# 04_-_Keyboard_Matrix_2.net
KiCad netlist of a schematic drawn in Altium Designer
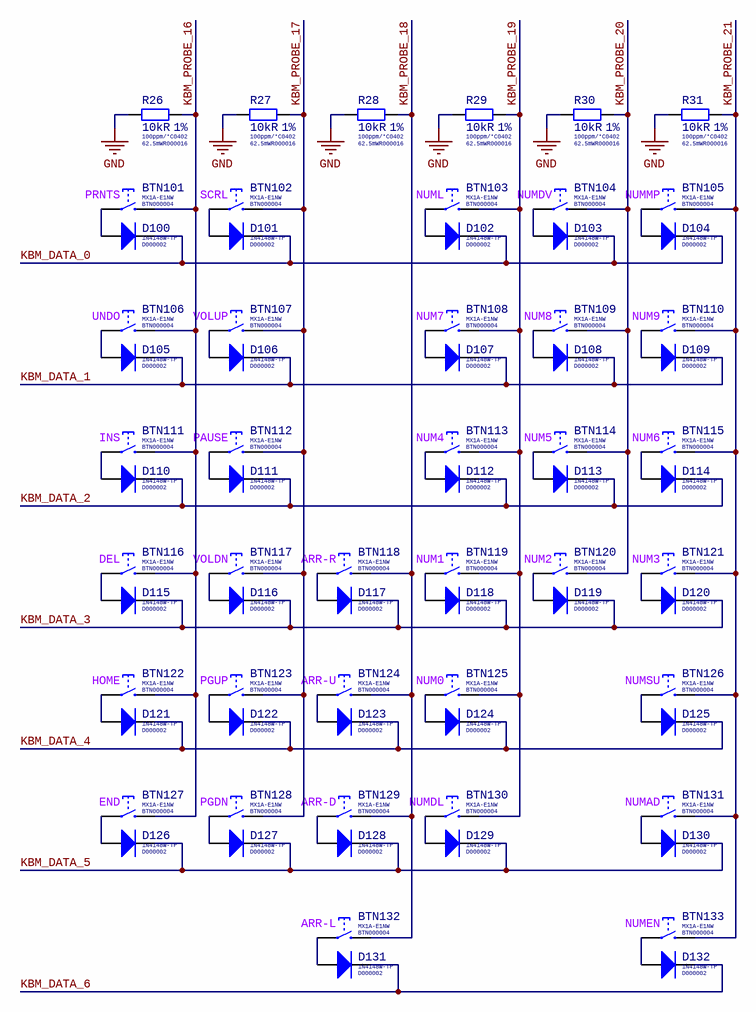
[diagram p0: [04] - Keyboard Matrix 2.SchDoc]

(export (version "E")
  (design (tool "Eeschema 10.0.6"))
  (components
    (comp (ref "BTN101")
      (value "MX1A-E1NW")
      (footprint "BTN-THT-MX-CHERRY")
      (description "BTN CHERRY MX BLUE SPST-NO 12V 10mA")
      (fields
        (field (name "MANUFACTURER") "Cherry")
        (field (name "INTERNAL PART NUMBER") "BTN000004")
        (field (name "KEY FUNCTION") "PRNTS")
      )
      (libsource (lib "Altium_Lib_Standard") (part "MX1A-E1NW"))
    )
    (comp (ref "BTN102")
      (value "MX1A-E1NW")
      (footprint "BTN-THT-MX-CHERRY")
      (description "BTN CHERRY MX BLUE SPST-NO 12V 10mA")
      (fields
        (field (name "MANUFACTURER") "Cherry")
        (field (name "INTERNAL PART NUMBER") "BTN000004")
        (field (name "KEY FUNCTION") "SCRL")
      )
      (libsource (lib "Altium_Lib_Standard") (part "MX1A-E1NW"))
    )
    (comp (ref "BTN103")
      (value "MX1A-E1NW")
      (footprint "BTN-THT-MX-CHERRY")
      (description "BTN CHERRY MX BLUE SPST-NO 12V 10mA")
      (fields
        (field (name "MANUFACTURER") "Cherry")
        (field (name "INTERNAL PART NUMBER") "BTN000004")
        (field (name "KEY FUNCTION") "NUML")
      )
      (libsource (lib "Altium_Lib_Standard") (part "MX1A-E1NW"))
    )
    (comp (ref "BTN104")
      (value "MX1A-E1NW")
      (footprint "BTN-THT-MX-CHERRY")
      (description "BTN CHERRY MX BLUE SPST-NO 12V 10mA")
      (fields
        (field (name "MANUFACTURER") "Cherry")
        (field (name "INTERNAL PART NUMBER") "BTN000004")
        (field (name "KEY FUNCTION") "NUMDV")
      )
      (libsource (lib "Altium_Lib_Standard") (part "MX1A-E1NW"))
    )
    (comp (ref "BTN105")
      (value "MX1A-E1NW")
      (footprint "BTN-THT-MX-CHERRY")
      (description "BTN CHERRY MX BLUE SPST-NO 12V 10mA")
      (fields
        (field (name "MANUFACTURER") "Cherry")
        (field (name "INTERNAL PART NUMBER") "BTN000004")
        (field (name "KEY FUNCTION") "NUMMP")
      )
      (libsource (lib "Altium_Lib_Standard") (part "MX1A-E1NW"))
    )
    (comp (ref "BTN106")
      (value "MX1A-E1NW")
      (footprint "BTN-THT-MX-CHERRY")
      (description "BTN CHERRY MX BLUE SPST-NO 12V 10mA")
      (fields
        (field (name "MANUFACTURER") "Cherry")
        (field (name "INTERNAL PART NUMBER") "BTN000004")
        (field (name "KEY FUNCTION") "UNDO")
      )
      (libsource (lib "Altium_Lib_Standard") (part "MX1A-E1NW"))
    )
    (comp (ref "BTN107")
      (value "MX1A-E1NW")
      (footprint "BTN-THT-MX-CHERRY")
      (description "BTN CHERRY MX BLUE SPST-NO 12V 10mA")
      (fields
        (field (name "MANUFACTURER") "Cherry")
        (field (name "INTERNAL PART NUMBER") "BTN000004")
        (field (name "KEY FUNCTION") "VOLUP")
      )
      (libsource (lib "Altium_Lib_Standard") (part "MX1A-E1NW"))
    )
    (comp (ref "BTN108")
      (value "MX1A-E1NW")
      (footprint "BTN-THT-MX-CHERRY")
      (description "BTN CHERRY MX BLUE SPST-NO 12V 10mA")
      (fields
        (field (name "MANUFACTURER") "Cherry")
        (field (name "INTERNAL PART NUMBER") "BTN000004")
        (field (name "KEY FUNCTION") "NUM7")
      )
      (libsource (lib "Altium_Lib_Standard") (part "MX1A-E1NW"))
    )
    (comp (ref "BTN109")
      (value "MX1A-E1NW")
      (footprint "BTN-THT-MX-CHERRY")
      (description "BTN CHERRY MX BLUE SPST-NO 12V 10mA")
      (fields
        (field (name "MANUFACTURER") "Cherry")
        (field (name "INTERNAL PART NUMBER") "BTN000004")
        (field (name "KEY FUNCTION") "NUM8")
      )
      (libsource (lib "Altium_Lib_Standard") (part "MX1A-E1NW"))
    )
    (comp (ref "BTN110")
      (value "MX1A-E1NW")
      (footprint "BTN-THT-MX-CHERRY")
      (description "BTN CHERRY MX BLUE SPST-NO 12V 10mA")
      (fields
        (field (name "MANUFACTURER") "Cherry")
        (field (name "INTERNAL PART NUMBER") "BTN000004")
        (field (name "KEY FUNCTION") "NUM9")
      )
      (libsource (lib "Altium_Lib_Standard") (part "MX1A-E1NW"))
    )
    (comp (ref "BTN111")
      (value "MX1A-E1NW")
      (footprint "BTN-THT-MX-CHERRY")
      (description "BTN CHERRY MX BLUE SPST-NO 12V 10mA")
      (fields
        (field (name "MANUFACTURER") "Cherry")
        (field (name "INTERNAL PART NUMBER") "BTN000004")
        (field (name "KEY FUNCTION") "INS")
      )
      (libsource (lib "Altium_Lib_Standard") (part "MX1A-E1NW"))
    )
    (comp (ref "BTN112")
      (value "MX1A-E1NW")
      (footprint "BTN-THT-MX-CHERRY")
      (description "BTN CHERRY MX BLUE SPST-NO 12V 10mA")
      (fields
        (field (name "MANUFACTURER") "Cherry")
        (field (name "INTERNAL PART NUMBER") "BTN000004")
        (field (name "KEY FUNCTION") "PAUSE")
      )
      (libsource (lib "Altium_Lib_Standard") (part "MX1A-E1NW"))
    )
    (comp (ref "BTN113")
      (value "MX1A-E1NW")
      (footprint "BTN-THT-MX-CHERRY")
      (description "BTN CHERRY MX BLUE SPST-NO 12V 10mA")
      (fields
        (field (name "MANUFACTURER") "Cherry")
        (field (name "INTERNAL PART NUMBER") "BTN000004")
        (field (name "KEY FUNCTION") "NUM4")
      )
      (libsource (lib "Altium_Lib_Standard") (part "MX1A-E1NW"))
    )
    (comp (ref "BTN114")
      (value "MX1A-E1NW")
      (footprint "BTN-THT-MX-CHERRY")
      (description "BTN CHERRY MX BLUE SPST-NO 12V 10mA")
      (fields
        (field (name "MANUFACTURER") "Cherry")
        (field (name "INTERNAL PART NUMBER") "BTN000004")
        (field (name "KEY FUNCTION") "NUM5")
      )
      (libsource (lib "Altium_Lib_Standard") (part "MX1A-E1NW"))
    )
    (comp (ref "BTN115")
      (value "MX1A-E1NW")
      (footprint "BTN-THT-MX-CHERRY")
      (description "BTN CHERRY MX BLUE SPST-NO 12V 10mA")
      (fields
        (field (name "MANUFACTURER") "Cherry")
        (field (name "INTERNAL PART NUMBER") "BTN000004")
        (field (name "KEY FUNCTION") "NUM6")
      )
      (libsource (lib "Altium_Lib_Standard") (part "MX1A-E1NW"))
    )
    (comp (ref "BTN116")
      (value "MX1A-E1NW")
      (footprint "BTN-THT-MX-CHERRY")
      (description "BTN CHERRY MX BLUE SPST-NO 12V 10mA")
      (fields
        (field (name "MANUFACTURER") "Cherry")
        (field (name "INTERNAL PART NUMBER") "BTN000004")
        (field (name "KEY FUNCTION") "DEL")
      )
      (libsource (lib "Altium_Lib_Standard") (part "MX1A-E1NW"))
    )
    (comp (ref "BTN117")
      (value "MX1A-E1NW")
      (footprint "BTN-THT-MX-CHERRY")
      (description "BTN CHERRY MX BLUE SPST-NO 12V 10mA")
      (fields
        (field (name "MANUFACTURER") "Cherry")
        (field (name "INTERNAL PART NUMBER") "BTN000004")
        (field (name "KEY FUNCTION") "VOLDN")
      )
      (libsource (lib "Altium_Lib_Standard") (part "MX1A-E1NW"))
    )
    (comp (ref "BTN118")
      (value "MX1A-E1NW")
      (footprint "BTN-THT-MX-CHERRY")
      (description "BTN CHERRY MX BLUE SPST-NO 12V 10mA")
      (fields
        (field (name "MANUFACTURER") "Cherry")
        (field (name "INTERNAL PART NUMBER") "BTN000004")
        (field (name "KEY FUNCTION") "ARR-R")
      )
      (libsource (lib "Altium_Lib_Standard") (part "MX1A-E1NW"))
    )
    (comp (ref "BTN119")
      (value "MX1A-E1NW")
      (footprint "BTN-THT-MX-CHERRY")
      (description "BTN CHERRY MX BLUE SPST-NO 12V 10mA")
      (fields
        (field (name "MANUFACTURER") "Cherry")
        (field (name "INTERNAL PART NUMBER") "BTN000004")
        (field (name "KEY FUNCTION") "NUM1")
      )
      (libsource (lib "Altium_Lib_Standard") (part "MX1A-E1NW"))
    )
    (comp (ref "BTN120")
      (value "MX1A-E1NW")
      (footprint "BTN-THT-MX-CHERRY")
      (description "BTN CHERRY MX BLUE SPST-NO 12V 10mA")
      (fields
        (field (name "MANUFACTURER") "Cherry")
        (field (name "INTERNAL PART NUMBER") "BTN000004")
        (field (name "KEY FUNCTION") "NUM2")
      )
      (libsource (lib "Altium_Lib_Standard") (part "MX1A-E1NW"))
    )
    (comp (ref "BTN121")
      (value "MX1A-E1NW")
      (footprint "BTN-THT-MX-CHERRY")
      (description "BTN CHERRY MX BLUE SPST-NO 12V 10mA")
      (fields
        (field (name "MANUFACTURER") "Cherry")
        (field (name "INTERNAL PART NUMBER") "BTN000004")
        (field (name "KEY FUNCTION") "NUM3")
      )
      (libsource (lib "Altium_Lib_Standard") (part "MX1A-E1NW"))
    )
    (comp (ref "BTN122")
      (value "MX1A-E1NW")
      (footprint "BTN-THT-MX-CHERRY")
      (description "BTN CHERRY MX BLUE SPST-NO 12V 10mA")
      (fields
        (field (name "MANUFACTURER") "Cherry")
        (field (name "INTERNAL PART NUMBER") "BTN000004")
        (field (name "KEY FUNCTION") "HOME")
      )
      (libsource (lib "Altium_Lib_Standard") (part "MX1A-E1NW"))
    )
    (comp (ref "BTN123")
      (value "MX1A-E1NW")
      (footprint "BTN-THT-MX-CHERRY")
      (description "BTN CHERRY MX BLUE SPST-NO 12V 10mA")
      (fields
        (field (name "MANUFACTURER") "Cherry")
        (field (name "INTERNAL PART NUMBER") "BTN000004")
        (field (name "KEY FUNCTION") "PGUP")
      )
      (libsource (lib "Altium_Lib_Standard") (part "MX1A-E1NW"))
    )
    (comp (ref "BTN124")
      (value "MX1A-E1NW")
      (footprint "BTN-THT-MX-CHERRY")
      (description "BTN CHERRY MX BLUE SPST-NO 12V 10mA")
      (fields
        (field (name "MANUFACTURER") "Cherry")
        (field (name "INTERNAL PART NUMBER") "BTN000004")
        (field (name "KEY FUNCTION") "ARR-U")
      )
      (libsource (lib "Altium_Lib_Standard") (part "MX1A-E1NW"))
    )
    (comp (ref "BTN125")
      (value "MX1A-E1NW")
      (footprint "BTN-THT-MX-CHERRY")
      (description "BTN CHERRY MX BLUE SPST-NO 12V 10mA")
      (fields
        (field (name "MANUFACTURER") "Cherry")
        (field (name "INTERNAL PART NUMBER") "BTN000004")
        (field (name "KEY FUNCTION") "NUM0")
      )
      (libsource (lib "Altium_Lib_Standard") (part "MX1A-E1NW"))
    )
    (comp (ref "BTN126")
      (value "MX1A-E1NW")
      (footprint "BTN-THT-MX-CHERRY")
      (description "BTN CHERRY MX BLUE SPST-NO 12V 10mA")
      (fields
        (field (name "MANUFACTURER") "Cherry")
        (field (name "INTERNAL PART NUMBER") "BTN000004")
        (field (name "KEY FUNCTION") "NUMSU")
      )
      (libsource (lib "Altium_Lib_Standard") (part "MX1A-E1NW"))
    )
    (comp (ref "BTN127")
      (value "MX1A-E1NW")
      (footprint "BTN-THT-MX-CHERRY")
      (description "BTN CHERRY MX BLUE SPST-NO 12V 10mA")
      (fields
        (field (name "MANUFACTURER") "Cherry")
        (field (name "INTERNAL PART NUMBER") "BTN000004")
        (field (name "KEY FUNCTION") "END")
      )
      (libsource (lib "Altium_Lib_Standard") (part "MX1A-E1NW"))
    )
    (comp (ref "BTN128")
      (value "MX1A-E1NW")
      (footprint "BTN-THT-MX-CHERRY")
      (description "BTN CHERRY MX BLUE SPST-NO 12V 10mA")
      (fields
        (field (name "MANUFACTURER") "Cherry")
        (field (name "INTERNAL PART NUMBER") "BTN000004")
        (field (name "KEY FUNCTION") "PGDN")
      )
      (libsource (lib "Altium_Lib_Standard") (part "MX1A-E1NW"))
    )
    (comp (ref "BTN129")
      (value "MX1A-E1NW")
      (footprint "BTN-THT-MX-CHERRY")
      (description "BTN CHERRY MX BLUE SPST-NO 12V 10mA")
      (fields
        (field (name "MANUFACTURER") "Cherry")
        (field (name "INTERNAL PART NUMBER") "BTN000004")
        (field (name "KEY FUNCTION") "ARR-D")
      )
      (libsource (lib "Altium_Lib_Standard") (part "MX1A-E1NW"))
    )
    (comp (ref "BTN130")
      (value "MX1A-E1NW")
      (footprint "BTN-THT-MX-CHERRY")
      (description "BTN CHERRY MX BLUE SPST-NO 12V 10mA")
      (fields
        (field (name "MANUFACTURER") "Cherry")
        (field (name "INTERNAL PART NUMBER") "BTN000004")
        (field (name "KEY FUNCTION") "NUMDL")
      )
      (libsource (lib "Altium_Lib_Standard") (part "MX1A-E1NW"))
    )
    (comp (ref "BTN131")
      (value "MX1A-E1NW")
      (footprint "BTN-THT-MX-CHERRY")
      (description "BTN CHERRY MX BLUE SPST-NO 12V 10mA")
      (fields
        (field (name "MANUFACTURER") "Cherry")
        (field (name "INTERNAL PART NUMBER") "BTN000004")
        (field (name "KEY FUNCTION") "NUMAD")
      )
      (libsource (lib "Altium_Lib_Standard") (part "MX1A-E1NW"))
    )
    (comp (ref "BTN132")
      (value "MX1A-E1NW")
      (footprint "BTN-THT-MX-CHERRY")
      (description "BTN CHERRY MX BLUE SPST-NO 12V 10mA")
      (fields
        (field (name "MANUFACTURER") "Cherry")
        (field (name "INTERNAL PART NUMBER") "BTN000004")
        (field (name "KEY FUNCTION") "ARR-L")
      )
      (libsource (lib "Altium_Lib_Standard") (part "MX1A-E1NW"))
    )
    (comp (ref "BTN133")
      (value "MX1A-E1NW")
      (footprint "BTN-THT-MX-CHERRY")
      (description "BTN CHERRY MX BLUE SPST-NO 12V 10mA")
      (fields
        (field (name "MANUFACTURER") "Cherry")
        (field (name "INTERNAL PART NUMBER") "BTN000004")
        (field (name "KEY FUNCTION") "NUMEN")
      )
      (libsource (lib "Altium_Lib_Standard") (part "MX1A-E1NW"))
    )
    (comp (ref "D100")
      (value "1N4148W-TP")
      (footprint "D-SMD-SOD-123-MICRO-COMMERCIAL-COMPONENTS")
      (description "DIODE GEN-PURP 100V 150mA 1V25@150mA SMD SOD-23")
      (fields (field (name "MANUFACTURER") "MCC") (field (name "INTERNAL PART NUMBER") "D000002"))
      (libsource (lib "Altium_Lib_Standard") (part "1N4148W-TP"))
    )
    (comp (ref "D101")
      (value "1N4148W-TP")
      (footprint "D-SMD-SOD-123-MICRO-COMMERCIAL-COMPONENTS")
      (description "DIODE GEN-PURP 100V 150mA 1V25@150mA SMD SOD-23")
      (fields (field (name "MANUFACTURER") "MCC") (field (name "INTERNAL PART NUMBER") "D000002"))
      (libsource (lib "Altium_Lib_Standard") (part "1N4148W-TP"))
    )
    (comp (ref "D102")
      (value "1N4148W-TP")
      (footprint "D-SMD-SOD-123-MICRO-COMMERCIAL-COMPONENTS")
      (description "DIODE GEN-PURP 100V 150mA 1V25@150mA SMD SOD-23")
      (fields (field (name "MANUFACTURER") "MCC") (field (name "INTERNAL PART NUMBER") "D000002"))
      (libsource (lib "Altium_Lib_Standard") (part "1N4148W-TP"))
    )
    (comp (ref "D103")
      (value "1N4148W-TP")
      (footprint "D-SMD-SOD-123-MICRO-COMMERCIAL-COMPONENTS")
      (description "DIODE GEN-PURP 100V 150mA 1V25@150mA SMD SOD-23")
      (fields (field (name "MANUFACTURER") "MCC") (field (name "INTERNAL PART NUMBER") "D000002"))
      (libsource (lib "Altium_Lib_Standard") (part "1N4148W-TP"))
    )
    (comp (ref "D104")
      (value "1N4148W-TP")
      (footprint "D-SMD-SOD-123-MICRO-COMMERCIAL-COMPONENTS")
      (description "DIODE GEN-PURP 100V 150mA 1V25@150mA SMD SOD-23")
      (fields (field (name "MANUFACTURER") "MCC") (field (name "INTERNAL PART NUMBER") "D000002"))
      (libsource (lib "Altium_Lib_Standard") (part "1N4148W-TP"))
    )
    (comp (ref "D105")
      (value "1N4148W-TP")
      (footprint "D-SMD-SOD-123-MICRO-COMMERCIAL-COMPONENTS")
      (description "DIODE GEN-PURP 100V 150mA 1V25@150mA SMD SOD-23")
      (fields (field (name "MANUFACTURER") "MCC") (field (name "INTERNAL PART NUMBER") "D000002"))
      (libsource (lib "Altium_Lib_Standard") (part "1N4148W-TP"))
    )
    (comp (ref "D106")
      (value "1N4148W-TP")
      (footprint "D-SMD-SOD-123-MICRO-COMMERCIAL-COMPONENTS")
      (description "DIODE GEN-PURP 100V 150mA 1V25@150mA SMD SOD-23")
      (fields (field (name "MANUFACTURER") "MCC") (field (name "INTERNAL PART NUMBER") "D000002"))
      (libsource (lib "Altium_Lib_Standard") (part "1N4148W-TP"))
    )
    (comp (ref "D107")
      (value "1N4148W-TP")
      (footprint "D-SMD-SOD-123-MICRO-COMMERCIAL-COMPONENTS")
      (description "DIODE GEN-PURP 100V 150mA 1V25@150mA SMD SOD-23")
      (fields (field (name "MANUFACTURER") "MCC") (field (name "INTERNAL PART NUMBER") "D000002"))
      (libsource (lib "Altium_Lib_Standard") (part "1N4148W-TP"))
    )
    (comp (ref "D108")
      (value "1N4148W-TP")
      (footprint "D-SMD-SOD-123-MICRO-COMMERCIAL-COMPONENTS")
      (description "DIODE GEN-PURP 100V 150mA 1V25@150mA SMD SOD-23")
      (fields (field (name "MANUFACTURER") "MCC") (field (name "INTERNAL PART NUMBER") "D000002"))
      (libsource (lib "Altium_Lib_Standard") (part "1N4148W-TP"))
    )
    (comp (ref "D109")
      (value "1N4148W-TP")
      (footprint "D-SMD-SOD-123-MICRO-COMMERCIAL-COMPONENTS")
      (description "DIODE GEN-PURP 100V 150mA 1V25@150mA SMD SOD-23")
      (fields (field (name "MANUFACTURER") "MCC") (field (name "INTERNAL PART NUMBER") "D000002"))
      (libsource (lib "Altium_Lib_Standard") (part "1N4148W-TP"))
    )
    (comp (ref "D110")
      (value "1N4148W-TP")
      (footprint "D-SMD-SOD-123-MICRO-COMMERCIAL-COMPONENTS")
      (description "DIODE GEN-PURP 100V 150mA 1V25@150mA SMD SOD-23")
      (fields (field (name "MANUFACTURER") "MCC") (field (name "INTERNAL PART NUMBER") "D000002"))
      (libsource (lib "Altium_Lib_Standard") (part "1N4148W-TP"))
    )
    (comp (ref "D111")
      (value "1N4148W-TP")
      (footprint "D-SMD-SOD-123-MICRO-COMMERCIAL-COMPONENTS")
      (description "DIODE GEN-PURP 100V 150mA 1V25@150mA SMD SOD-23")
      (fields (field (name "MANUFACTURER") "MCC") (field (name "INTERNAL PART NUMBER") "D000002"))
      (libsource (lib "Altium_Lib_Standard") (part "1N4148W-TP"))
    )
    (comp (ref "D112")
      (value "1N4148W-TP")
      (footprint "D-SMD-SOD-123-MICRO-COMMERCIAL-COMPONENTS")
      (description "DIODE GEN-PURP 100V 150mA 1V25@150mA SMD SOD-23")
      (fields (field (name "MANUFACTURER") "MCC") (field (name "INTERNAL PART NUMBER") "D000002"))
      (libsource (lib "Altium_Lib_Standard") (part "1N4148W-TP"))
    )
    (comp (ref "D113")
      (value "1N4148W-TP")
      (footprint "D-SMD-SOD-123-MICRO-COMMERCIAL-COMPONENTS")
      (description "DIODE GEN-PURP 100V 150mA 1V25@150mA SMD SOD-23")
      (fields (field (name "MANUFACTURER") "MCC") (field (name "INTERNAL PART NUMBER") "D000002"))
      (libsource (lib "Altium_Lib_Standard") (part "1N4148W-TP"))
    )
    (comp (ref "D114")
      (value "1N4148W-TP")
      (footprint "D-SMD-SOD-123-MICRO-COMMERCIAL-COMPONENTS")
      (description "DIODE GEN-PURP 100V 150mA 1V25@150mA SMD SOD-23")
      (fields (field (name "MANUFACTURER") "MCC") (field (name "INTERNAL PART NUMBER") "D000002"))
      (libsource (lib "Altium_Lib_Standard") (part "1N4148W-TP"))
    )
    (comp (ref "D115")
      (value "1N4148W-TP")
      (footprint "D-SMD-SOD-123-MICRO-COMMERCIAL-COMPONENTS")
      (description "DIODE GEN-PURP 100V 150mA 1V25@150mA SMD SOD-23")
      (fields (field (name "MANUFACTURER") "MCC") (field (name "INTERNAL PART NUMBER") "D000002"))
      (libsource (lib "Altium_Lib_Standard") (part "1N4148W-TP"))
    )
    (comp (ref "D116")
      (value "1N4148W-TP")
      (footprint "D-SMD-SOD-123-MICRO-COMMERCIAL-COMPONENTS")
      (description "DIODE GEN-PURP 100V 150mA 1V25@150mA SMD SOD-23")
      (fields (field (name "MANUFACTURER") "MCC") (field (name "INTERNAL PART NUMBER") "D000002"))
      (libsource (lib "Altium_Lib_Standard") (part "1N4148W-TP"))
    )
    (comp (ref "D117")
      (value "1N4148W-TP")
      (footprint "D-SMD-SOD-123-MICRO-COMMERCIAL-COMPONENTS")
      (description "DIODE GEN-PURP 100V 150mA 1V25@150mA SMD SOD-23")
      (fields (field (name "MANUFACTURER") "MCC") (field (name "INTERNAL PART NUMBER") "D000002"))
      (libsource (lib "Altium_Lib_Standard") (part "1N4148W-TP"))
    )
    (comp (ref "D118")
      (value "1N4148W-TP")
      (footprint "D-SMD-SOD-123-MICRO-COMMERCIAL-COMPONENTS")
      (description "DIODE GEN-PURP 100V 150mA 1V25@150mA SMD SOD-23")
      (fields (field (name "MANUFACTURER") "MCC") (field (name "INTERNAL PART NUMBER") "D000002"))
      (libsource (lib "Altium_Lib_Standard") (part "1N4148W-TP"))
    )
    (comp (ref "D119")
      (value "1N4148W-TP")
      (footprint "D-SMD-SOD-123-MICRO-COMMERCIAL-COMPONENTS")
      (description "DIODE GEN-PURP 100V 150mA 1V25@150mA SMD SOD-23")
      (fields (field (name "MANUFACTURER") "MCC") (field (name "INTERNAL PART NUMBER") "D000002"))
      (libsource (lib "Altium_Lib_Standard") (part "1N4148W-TP"))
    )
    (comp (ref "D120")
      (value "1N4148W-TP")
      (footprint "D-SMD-SOD-123-MICRO-COMMERCIAL-COMPONENTS")
      (description "DIODE GEN-PURP 100V 150mA 1V25@150mA SMD SOD-23")
      (fields (field (name "MANUFACTURER") "MCC") (field (name "INTERNAL PART NUMBER") "D000002"))
      (libsource (lib "Altium_Lib_Standard") (part "1N4148W-TP"))
    )
    (comp (ref "D121")
      (value "1N4148W-TP")
      (footprint "D-SMD-SOD-123-MICRO-COMMERCIAL-COMPONENTS")
      (description "DIODE GEN-PURP 100V 150mA 1V25@150mA SMD SOD-23")
      (fields (field (name "MANUFACTURER") "MCC") (field (name "INTERNAL PART NUMBER") "D000002"))
      (libsource (lib "Altium_Lib_Standard") (part "1N4148W-TP"))
    )
    (comp (ref "D122")
      (value "1N4148W-TP")
      (footprint "D-SMD-SOD-123-MICRO-COMMERCIAL-COMPONENTS")
      (description "DIODE GEN-PURP 100V 150mA 1V25@150mA SMD SOD-23")
      (fields (field (name "MANUFACTURER") "MCC") (field (name "INTERNAL PART NUMBER") "D000002"))
      (libsource (lib "Altium_Lib_Standard") (part "1N4148W-TP"))
    )
    (comp (ref "D123")
      (value "1N4148W-TP")
      (footprint "D-SMD-SOD-123-MICRO-COMMERCIAL-COMPONENTS")
      (description "DIODE GEN-PURP 100V 150mA 1V25@150mA SMD SOD-23")
      (fields (field (name "MANUFACTURER") "MCC") (field (name "INTERNAL PART NUMBER") "D000002"))
      (libsource (lib "Altium_Lib_Standard") (part "1N4148W-TP"))
    )
    (comp (ref "D124")
      (value "1N4148W-TP")
      (footprint "D-SMD-SOD-123-MICRO-COMMERCIAL-COMPONENTS")
      (description "DIODE GEN-PURP 100V 150mA 1V25@150mA SMD SOD-23")
      (fields (field (name "MANUFACTURER") "MCC") (field (name "INTERNAL PART NUMBER") "D000002"))
      (libsource (lib "Altium_Lib_Standard") (part "1N4148W-TP"))
    )
    (comp (ref "D125")
      (value "1N4148W-TP")
      (footprint "D-SMD-SOD-123-MICRO-COMMERCIAL-COMPONENTS")
      (description "DIODE GEN-PURP 100V 150mA 1V25@150mA SMD SOD-23")
      (fields (field (name "MANUFACTURER") "MCC") (field (name "INTERNAL PART NUMBER") "D000002"))
      (libsource (lib "Altium_Lib_Standard") (part "1N4148W-TP"))
    )
    (comp (ref "D126")
      (value "1N4148W-TP")
      (footprint "D-SMD-SOD-123-MICRO-COMMERCIAL-COMPONENTS")
      (description "DIODE GEN-PURP 100V 150mA 1V25@150mA SMD SOD-23")
      (fields (field (name "MANUFACTURER") "MCC") (field (name "INTERNAL PART NUMBER") "D000002"))
      (libsource (lib "Altium_Lib_Standard") (part "1N4148W-TP"))
    )
    (comp (ref "D127")
      (value "1N4148W-TP")
      (footprint "D-SMD-SOD-123-MICRO-COMMERCIAL-COMPONENTS")
      (description "DIODE GEN-PURP 100V 150mA 1V25@150mA SMD SOD-23")
      (fields (field (name "MANUFACTURER") "MCC") (field (name "INTERNAL PART NUMBER") "D000002"))
      (libsource (lib "Altium_Lib_Standard") (part "1N4148W-TP"))
    )
    (comp (ref "D128")
      (value "1N4148W-TP")
      (footprint "D-SMD-SOD-123-MICRO-COMMERCIAL-COMPONENTS")
      (description "DIODE GEN-PURP 100V 150mA 1V25@150mA SMD SOD-23")
      (fields (field (name "MANUFACTURER") "MCC") (field (name "INTERNAL PART NUMBER") "D000002"))
      (libsource (lib "Altium_Lib_Standard") (part "1N4148W-TP"))
    )
    (comp (ref "D129")
      (value "1N4148W-TP")
      (footprint "D-SMD-SOD-123-MICRO-COMMERCIAL-COMPONENTS")
      (description "DIODE GEN-PURP 100V 150mA 1V25@150mA SMD SOD-23")
      (fields (field (name "MANUFACTURER") "MCC") (field (name "INTERNAL PART NUMBER") "D000002"))
      (libsource (lib "Altium_Lib_Standard") (part "1N4148W-TP"))
    )
    (comp (ref "D130")
      (value "1N4148W-TP")
      (footprint "D-SMD-SOD-123-MICRO-COMMERCIAL-COMPONENTS")
      (description "DIODE GEN-PURP 100V 150mA 1V25@150mA SMD SOD-23")
      (fields (field (name "MANUFACTURER") "MCC") (field (name "INTERNAL PART NUMBER") "D000002"))
      (libsource (lib "Altium_Lib_Standard") (part "1N4148W-TP"))
    )
    (comp (ref "D131")
      (value "1N4148W-TP")
      (footprint "D-SMD-SOD-123-MICRO-COMMERCIAL-COMPONENTS")
      (description "DIODE GEN-PURP 100V 150mA 1V25@150mA SMD SOD-23")
      (fields (field (name "MANUFACTURER") "MCC") (field (name "INTERNAL PART NUMBER") "D000002"))
      (libsource (lib "Altium_Lib_Standard") (part "1N4148W-TP"))
    )
    (comp (ref "D132")
      (value "1N4148W-TP")
      (footprint "D-SMD-SOD-123-MICRO-COMMERCIAL-COMPONENTS")
      (description "DIODE GEN-PURP 100V 150mA 1V25@150mA SMD SOD-23")
      (fields (field (name "MANUFACTURER") "MCC") (field (name "INTERNAL PART NUMBER") "D000002"))
      (libsource (lib "Altium_Lib_Standard") (part "1N4148W-TP"))
    )
    (comp (ref "R26")
      (value "10kR 1%")
      (footprint "RES-SMD-0402-0.4MM-IPC-MED")
      (description "RES 10K 1% 1/16W SMD 0402 YAEGO")
      (fields
        (field (name "MANUFACTURER") "Yageo")
        (field (name "MANUFACTURER PART NUMBER") "RC0402FR-0710KL")
        (field (name "TOLERANCE") "1%")
        (field (name "TEMPERATURE COEFFICIENT") "100ppm/°C")
        (field (name "RESISTANCE") "10kR")
        (field (name "POWER RATING") "62.5mW")
        (field (name "CASE CODE (IMPERIAL)") "0402")
        (field (name "INTERNAL PART NUMBER") "R000016")
      )
      (libsource (lib "Altium_Lib_Standard") (part "RC0402FR-0710KL"))
    )
    (comp (ref "R27")
      (value "10kR 1%")
      (footprint "RES-SMD-0402-0.4MM-IPC-MED")
      (description "RES 10K 1% 1/16W SMD 0402 YAEGO")
      (fields
        (field (name "MANUFACTURER") "Yageo")
        (field (name "MANUFACTURER PART NUMBER") "RC0402FR-0710KL")
        (field (name "TOLERANCE") "1%")
        (field (name "TEMPERATURE COEFFICIENT") "100ppm/°C")
        (field (name "RESISTANCE") "10kR")
        (field (name "POWER RATING") "62.5mW")
        (field (name "CASE CODE (IMPERIAL)") "0402")
        (field (name "INTERNAL PART NUMBER") "R000016")
      )
      (libsource (lib "Altium_Lib_Standard") (part "RC0402FR-0710KL"))
    )
    (comp (ref "R28")
      (value "10kR 1%")
      (footprint "RES-SMD-0402-0.4MM-IPC-MED")
      (description "RES 10K 1% 1/16W SMD 0402 YAEGO")
      (fields
        (field (name "MANUFACTURER") "Yageo")
        (field (name "MANUFACTURER PART NUMBER") "RC0402FR-0710KL")
        (field (name "TOLERANCE") "1%")
        (field (name "TEMPERATURE COEFFICIENT") "100ppm/°C")
        (field (name "RESISTANCE") "10kR")
        (field (name "POWER RATING") "62.5mW")
        (field (name "CASE CODE (IMPERIAL)") "0402")
        (field (name "INTERNAL PART NUMBER") "R000016")
      )
      (libsource (lib "Altium_Lib_Standard") (part "RC0402FR-0710KL"))
    )
    (comp (ref "R29")
      (value "10kR 1%")
      (footprint "RES-SMD-0402-0.4MM-IPC-MED")
      (description "RES 10K 1% 1/16W SMD 0402 YAEGO")
      (fields
        (field (name "MANUFACTURER") "Yageo")
        (field (name "MANUFACTURER PART NUMBER") "RC0402FR-0710KL")
        (field (name "TOLERANCE") "1%")
        (field (name "TEMPERATURE COEFFICIENT") "100ppm/°C")
        (field (name "RESISTANCE") "10kR")
        (field (name "POWER RATING") "62.5mW")
        (field (name "CASE CODE (IMPERIAL)") "0402")
        (field (name "INTERNAL PART NUMBER") "R000016")
      )
      (libsource (lib "Altium_Lib_Standard") (part "RC0402FR-0710KL"))
    )
    (comp (ref "R30")
      (value "10kR 1%")
      (footprint "RES-SMD-0402-0.4MM-IPC-MED")
      (description "RES 10K 1% 1/16W SMD 0402 YAEGO")
      (fields
        (field (name "MANUFACTURER") "Yageo")
        (field (name "MANUFACTURER PART NUMBER") "RC0402FR-0710KL")
        (field (name "TOLERANCE") "1%")
        (field (name "TEMPERATURE COEFFICIENT") "100ppm/°C")
        (field (name "RESISTANCE") "10kR")
        (field (name "POWER RATING") "62.5mW")
        (field (name "CASE CODE (IMPERIAL)") "0402")
        (field (name "INTERNAL PART NUMBER") "R000016")
      )
      (libsource (lib "Altium_Lib_Standard") (part "RC0402FR-0710KL"))
    )
    (comp (ref "R31")
      (value "10kR 1%")
      (footprint "RES-SMD-0402-0.4MM-IPC-MED")
      (description "RES 10K 1% 1/16W SMD 0402 YAEGO")
      (fields
        (field (name "MANUFACTURER") "Yageo")
        (field (name "MANUFACTURER PART NUMBER") "RC0402FR-0710KL")
        (field (name "TOLERANCE") "1%")
        (field (name "TEMPERATURE COEFFICIENT") "100ppm/°C")
        (field (name "RESISTANCE") "10kR")
        (field (name "POWER RATING") "62.5mW")
        (field (name "CASE CODE (IMPERIAL)") "0402")
        (field (name "INTERNAL PART NUMBER") "R000016")
      )
      (libsource (lib "Altium_Lib_Standard") (part "RC0402FR-0710KL"))
    )
  )
  (nets
    (net (code "1") (name "/KBM_DATA_0") (class "Default")
      (node (ref "D100") (pin "1") (pinfunction "1_1") (pintype "passive"))
      (node (ref "D101") (pin "1") (pinfunction "1_1") (pintype "passive"))
      (node (ref "D102") (pin "1") (pinfunction "1_1") (pintype "passive"))
      (node (ref "D103") (pin "1") (pinfunction "1_1") (pintype "passive"))
      (node (ref "D104") (pin "1") (pinfunction "1_1") (pintype "passive"))
    )
    (net (code "2") (name "/KBM_DATA_1") (class "Default")
      (node (ref "D105") (pin "1") (pinfunction "1_1") (pintype "passive"))
      (node (ref "D106") (pin "1") (pinfunction "1_1") (pintype "passive"))
      (node (ref "D107") (pin "1") (pinfunction "1_1") (pintype "passive"))
      (node (ref "D108") (pin "1") (pinfunction "1_1") (pintype "passive"))
      (node (ref "D109") (pin "1") (pinfunction "1_1") (pintype "passive"))
    )
    (net (code "3") (name "/KBM_DATA_2") (class "Default")
      (node (ref "D110") (pin "1") (pinfunction "1_1") (pintype "passive"))
      (node (ref "D111") (pin "1") (pinfunction "1_1") (pintype "passive"))
      (node (ref "D112") (pin "1") (pinfunction "1_1") (pintype "passive"))
      (node (ref "D113") (pin "1") (pinfunction "1_1") (pintype "passive"))
      (node (ref "D114") (pin "1") (pinfunction "1_1") (pintype "passive"))
    )
    (net (code "4") (name "/KBM_DATA_3") (class "Default")
      (node (ref "D115") (pin "1") (pinfunction "1_1") (pintype "passive"))
      (node (ref "D116") (pin "1") (pinfunction "1_1") (pintype "passive"))
      (node (ref "D117") (pin "1") (pinfunction "1_1") (pintype "passive"))
      (node (ref "D118") (pin "1") (pinfunction "1_1") (pintype "passive"))
      (node (ref "D119") (pin "1") (pinfunction "1_1") (pintype "passive"))
      (node (ref "D120") (pin "1") (pinfunction "1_1") (pintype "passive"))
    )
    (net (code "5") (name "/KBM_DATA_4") (class "Default")
      (node (ref "D121") (pin "1") (pinfunction "1_1") (pintype "passive"))
      (node (ref "D122") (pin "1") (pinfunction "1_1") (pintype "passive"))
      (node (ref "D123") (pin "1") (pinfunction "1_1") (pintype "passive"))
      (node (ref "D124") (pin "1") (pinfunction "1_1") (pintype "passive"))
      (node (ref "D125") (pin "1") (pinfunction "1_1") (pintype "passive"))
    )
    (net (code "6") (name "/KBM_DATA_5") (class "Default")
      (node (ref "D126") (pin "1") (pinfunction "1_1") (pintype "passive"))
      (node (ref "D127") (pin "1") (pinfunction "1_1") (pintype "passive"))
      (node (ref "D128") (pin "1") (pinfunction "1_1") (pintype "passive"))
      (node (ref "D129") (pin "1") (pinfunction "1_1") (pintype "passive"))
      (node (ref "D130") (pin "1") (pinfunction "1_1") (pintype "passive"))
    )
    (net (code "7") (name "/KBM_DATA_6") (class "Default")
      (node (ref "D131") (pin "1") (pinfunction "1_1") (pintype "passive"))
      (node (ref "D132") (pin "1") (pinfunction "1_1") (pintype "passive"))
    )
    (net (code "8") (name "/KBM_PROBE_16") (class "Default")
      (node (ref "BTN101") (pin "2") (pinfunction "2_2") (pintype "passive"))
      (node (ref "BTN106") (pin "2") (pinfunction "2_2") (pintype "passive"))
      (node (ref "BTN111") (pin "2") (pinfunction "2_2") (pintype "passive"))
      (node (ref "BTN116") (pin "2") (pinfunction "2_2") (pintype "passive"))
      (node (ref "BTN122") (pin "2") (pinfunction "2_2") (pintype "passive"))
      (node (ref "BTN127") (pin "2") (pinfunction "2_2") (pintype "passive"))
      (node (ref "R26") (pin "2") (pinfunction "2_2") (pintype "passive"))
    )
    (net (code "9") (name "/KBM_PROBE_17") (class "Default")
      (node (ref "BTN102") (pin "2") (pinfunction "2_2") (pintype "passive"))
      (node (ref "BTN107") (pin "2") (pinfunction "2_2") (pintype "passive"))
      (node (ref "BTN112") (pin "2") (pinfunction "2_2") (pintype "passive"))
      (node (ref "BTN117") (pin "2") (pinfunction "2_2") (pintype "passive"))
      (node (ref "BTN123") (pin "2") (pinfunction "2_2") (pintype "passive"))
      (node (ref "BTN128") (pin "2") (pinfunction "2_2") (pintype "passive"))
      (node (ref "R27") (pin "2") (pinfunction "2_2") (pintype "passive"))
    )
    (net (code "10") (name "/KBM_PROBE_18") (class "Default")
      (node (ref "BTN118") (pin "2") (pinfunction "2_2") (pintype "passive"))
      (node (ref "BTN124") (pin "2") (pinfunction "2_2") (pintype "passive"))
      (node (ref "BTN129") (pin "2") (pinfunction "2_2") (pintype "passive"))
      (node (ref "BTN132") (pin "2") (pinfunction "2_2") (pintype "passive"))
      (node (ref "R28") (pin "2") (pinfunction "2_2") (pintype "passive"))
    )
    (net (code "11") (name "/KBM_PROBE_19") (class "Default")
      (node (ref "BTN103") (pin "2") (pinfunction "2_2") (pintype "passive"))
      (node (ref "BTN108") (pin "2") (pinfunction "2_2") (pintype "passive"))
      (node (ref "BTN113") (pin "2") (pinfunction "2_2") (pintype "passive"))
      (node (ref "BTN119") (pin "2") (pinfunction "2_2") (pintype "passive"))
      (node (ref "BTN125") (pin "2") (pinfunction "2_2") (pintype "passive"))
      (node (ref "BTN130") (pin "2") (pinfunction "2_2") (pintype "passive"))
      (node (ref "R29") (pin "2") (pinfunction "2_2") (pintype "passive"))
    )
    (net (code "12") (name "/KBM_PROBE_20") (class "Default")
      (node (ref "BTN104") (pin "2") (pinfunction "2_2") (pintype "passive"))
      (node (ref "BTN109") (pin "2") (pinfunction "2_2") (pintype "passive"))
      (node (ref "BTN114") (pin "2") (pinfunction "2_2") (pintype "passive"))
      (node (ref "BTN120") (pin "2") (pinfunction "2_2") (pintype "passive"))
      (node (ref "R30") (pin "2") (pinfunction "2_2") (pintype "passive"))
    )
    (net (code "13") (name "/KBM_PROBE_21") (class "Default")
      (node (ref "BTN105") (pin "2") (pinfunction "2_2") (pintype "passive"))
      (node (ref "BTN110") (pin "2") (pinfunction "2_2") (pintype "passive"))
      (node (ref "BTN115") (pin "2") (pinfunction "2_2") (pintype "passive"))
      (node (ref "BTN121") (pin "2") (pinfunction "2_2") (pintype "passive"))
      (node (ref "BTN126") (pin "2") (pinfunction "2_2") (pintype "passive"))
      (node (ref "BTN131") (pin "2") (pinfunction "2_2") (pintype "passive"))
      (node (ref "BTN133") (pin "2") (pinfunction "2_2") (pintype "passive"))
      (node (ref "R31") (pin "2") (pinfunction "2_2") (pintype "passive"))
    )
    (net (code "14") (name "GND") (class "Default")
      (node (ref "R26") (pin "1") (pinfunction "1_1") (pintype "passive"))
      (node (ref "R27") (pin "1") (pinfunction "1_1") (pintype "passive"))
      (node (ref "R28") (pin "1") (pinfunction "1_1") (pintype "passive"))
      (node (ref "R29") (pin "1") (pinfunction "1_1") (pintype "passive"))
      (node (ref "R30") (pin "1") (pinfunction "1_1") (pintype "passive"))
      (node (ref "R31") (pin "1") (pinfunction "1_1") (pintype "passive"))
    )
    (net (code "15") (name "Net-(BTN101-Pad1)") (class "Default")
      (node (ref "BTN101") (pin "1") (pinfunction "1_1") (pintype "passive"))
      (node (ref "D100") (pin "2") (pinfunction "2_2") (pintype "passive"))
    )
    (net (code "16") (name "Net-(BTN102-Pad1)") (class "Default")
      (node (ref "BTN102") (pin "1") (pinfunction "1_1") (pintype "passive"))
      (node (ref "D101") (pin "2") (pinfunction "2_2") (pintype "passive"))
    )
    (net (code "17") (name "Net-(BTN103-Pad1)") (class "Default")
      (node (ref "BTN103") (pin "1") (pinfunction "1_1") (pintype "passive"))
      (node (ref "D102") (pin "2") (pinfunction "2_2") (pintype "passive"))
    )
    (net (code "18") (name "Net-(BTN104-Pad1)") (class "Default")
      (node (ref "BTN104") (pin "1") (pinfunction "1_1") (pintype "passive"))
      (node (ref "D103") (pin "2") (pinfunction "2_2") (pintype "passive"))
    )
    (net (code "19") (name "Net-(BTN105-Pad1)") (class "Default")
      (node (ref "BTN105") (pin "1") (pinfunction "1_1") (pintype "passive"))
      (node (ref "D104") (pin "2") (pinfunction "2_2") (pintype "passive"))
    )
    (net (code "20") (name "Net-(BTN106-Pad1)") (class "Default")
      (node (ref "BTN106") (pin "1") (pinfunction "1_1") (pintype "passive"))
      (node (ref "D105") (pin "2") (pinfunction "2_2") (pintype "passive"))
    )
    (net (code "21") (name "Net-(BTN107-Pad1)") (class "Default")
      (node (ref "BTN107") (pin "1") (pinfunction "1_1") (pintype "passive"))
      (node (ref "D106") (pin "2") (pinfunction "2_2") (pintype "passive"))
    )
    (net (code "22") (name "Net-(BTN108-Pad1)") (class "Default")
      (node (ref "BTN108") (pin "1") (pinfunction "1_1") (pintype "passive"))
      (node (ref "D107") (pin "2") (pinfunction "2_2") (pintype "passive"))
    )
    (net (code "23") (name "Net-(BTN109-Pad1)") (class "Default")
      (node (ref "BTN109") (pin "1") (pinfunction "1_1") (pintype "passive"))
      (node (ref "D108") (pin "2") (pinfunction "2_2") (pintype "passive"))
    )
    (net (code "24") (name "Net-(BTN110-Pad1)") (class "Default")
      (node (ref "BTN110") (pin "1") (pinfunction "1_1") (pintype "passive"))
      (node (ref "D109") (pin "2") (pinfunction "2_2") (pintype "passive"))
    )
    (net (code "25") (name "Net-(BTN111-Pad1)") (class "Default")
      (node (ref "BTN111") (pin "1") (pinfunction "1_1") (pintype "passive"))
      (node (ref "D110") (pin "2") (pinfunction "2_2") (pintype "passive"))
    )
    (net (code "26") (name "Net-(BTN112-Pad1)") (class "Default")
      (node (ref "BTN112") (pin "1") (pinfunction "1_1") (pintype "passive"))
      (node (ref "D111") (pin "2") (pinfunction "2_2") (pintype "passive"))
    )
    (net (code "27") (name "Net-(BTN113-Pad1)") (class "Default")
      (node (ref "BTN113") (pin "1") (pinfunction "1_1") (pintype "passive"))
      (node (ref "D112") (pin "2") (pinfunction "2_2") (pintype "passive"))
    )
    (net (code "28") (name "Net-(BTN114-Pad1)") (class "Default")
      (node (ref "BTN114") (pin "1") (pinfunction "1_1") (pintype "passive"))
      (node (ref "D113") (pin "2") (pinfunction "2_2") (pintype "passive"))
    )
    (net (code "29") (name "Net-(BTN115-Pad1)") (class "Default")
      (node (ref "BTN115") (pin "1") (pinfunction "1_1") (pintype "passive"))
      (node (ref "D114") (pin "2") (pinfunction "2_2") (pintype "passive"))
    )
    (net (code "30") (name "Net-(BTN116-Pad1)") (class "Default")
      (node (ref "BTN116") (pin "1") (pinfunction "1_1") (pintype "passive"))
      (node (ref "D115") (pin "2") (pinfunction "2_2") (pintype "passive"))
    )
    (net (code "31") (name "Net-(BTN117-Pad1)") (class "Default")
      (node (ref "BTN117") (pin "1") (pinfunction "1_1") (pintype "passive"))
      (node (ref "D116") (pin "2") (pinfunction "2_2") (pintype "passive"))
    )
    (net (code "32") (name "Net-(BTN118-Pad1)") (class "Default")
      (node (ref "BTN118") (pin "1") (pinfunction "1_1") (pintype "passive"))
      (node (ref "D117") (pin "2") (pinfunction "2_2") (pintype "passive"))
    )
    (net (code "33") (name "Net-(BTN119-Pad1)") (class "Default")
      (node (ref "BTN119") (pin "1") (pinfunction "1_1") (pintype "passive"))
      (node (ref "D118") (pin "2") (pinfunction "2_2") (pintype "passive"))
    )
    (net (code "34") (name "Net-(BTN120-Pad1)") (class "Default")
      (node (ref "BTN120") (pin "1") (pinfunction "1_1") (pintype "passive"))
      (node (ref "D119") (pin "2") (pinfunction "2_2") (pintype "passive"))
    )
    (net (code "35") (name "Net-(BTN121-Pad1)") (class "Default")
      (node (ref "BTN121") (pin "1") (pinfunction "1_1") (pintype "passive"))
      (node (ref "D120") (pin "2") (pinfunction "2_2") (pintype "passive"))
    )
    (net (code "36") (name "Net-(BTN122-Pad1)") (class "Default")
      (node (ref "BTN122") (pin "1") (pinfunction "1_1") (pintype "passive"))
      (node (ref "D121") (pin "2") (pinfunction "2_2") (pintype "passive"))
    )
    (net (code "37") (name "Net-(BTN123-Pad1)") (class "Default")
      (node (ref "BTN123") (pin "1") (pinfunction "1_1") (pintype "passive"))
      (node (ref "D122") (pin "2") (pinfunction "2_2") (pintype "passive"))
    )
    (net (code "38") (name "Net-(BTN124-Pad1)") (class "Default")
      (node (ref "BTN124") (pin "1") (pinfunction "1_1") (pintype "passive"))
      (node (ref "D123") (pin "2") (pinfunction "2_2") (pintype "passive"))
    )
    (net (code "39") (name "Net-(BTN125-Pad1)") (class "Default")
      (node (ref "BTN125") (pin "1") (pinfunction "1_1") (pintype "passive"))
      (node (ref "D124") (pin "2") (pinfunction "2_2") (pintype "passive"))
    )
    (net (code "40") (name "Net-(BTN126-Pad1)") (class "Default")
      (node (ref "BTN126") (pin "1") (pinfunction "1_1") (pintype "passive"))
      (node (ref "D125") (pin "2") (pinfunction "2_2") (pintype "passive"))
    )
    (net (code "41") (name "Net-(BTN127-Pad1)") (class "Default")
      (node (ref "BTN127") (pin "1") (pinfunction "1_1") (pintype "passive"))
      (node (ref "D126") (pin "2") (pinfunction "2_2") (pintype "passive"))
    )
    (net (code "42") (name "Net-(BTN128-Pad1)") (class "Default")
      (node (ref "BTN128") (pin "1") (pinfunction "1_1") (pintype "passive"))
      (node (ref "D127") (pin "2") (pinfunction "2_2") (pintype "passive"))
    )
    (net (code "43") (name "Net-(BTN129-Pad1)") (class "Default")
      (node (ref "BTN129") (pin "1") (pinfunction "1_1") (pintype "passive"))
      (node (ref "D128") (pin "2") (pinfunction "2_2") (pintype "passive"))
    )
    (net (code "44") (name "Net-(BTN130-Pad1)") (class "Default")
      (node (ref "BTN130") (pin "1") (pinfunction "1_1") (pintype "passive"))
      (node (ref "D129") (pin "2") (pinfunction "2_2") (pintype "passive"))
    )
    (net (code "45") (name "Net-(BTN131-Pad1)") (class "Default")
      (node (ref "BTN131") (pin "1") (pinfunction "1_1") (pintype "passive"))
      (node (ref "D130") (pin "2") (pinfunction "2_2") (pintype "passive"))
    )
    (net (code "46") (name "Net-(BTN132-Pad1)") (class "Default")
      (node (ref "BTN132") (pin "1") (pinfunction "1_1") (pintype "passive"))
      (node (ref "D131") (pin "2") (pinfunction "2_2") (pintype "passive"))
    )
    (net (code "47") (name "Net-(BTN133-Pad1)") (class "Default")
      (node (ref "BTN133") (pin "1") (pinfunction "1_1") (pintype "passive"))
      (node (ref "D132") (pin "2") (pinfunction "2_2") (pintype "passive"))
    )
  )
)
